# C-06_BOOT_CFG.net
KiCad netlist of a schematic drawn in Altium Designer
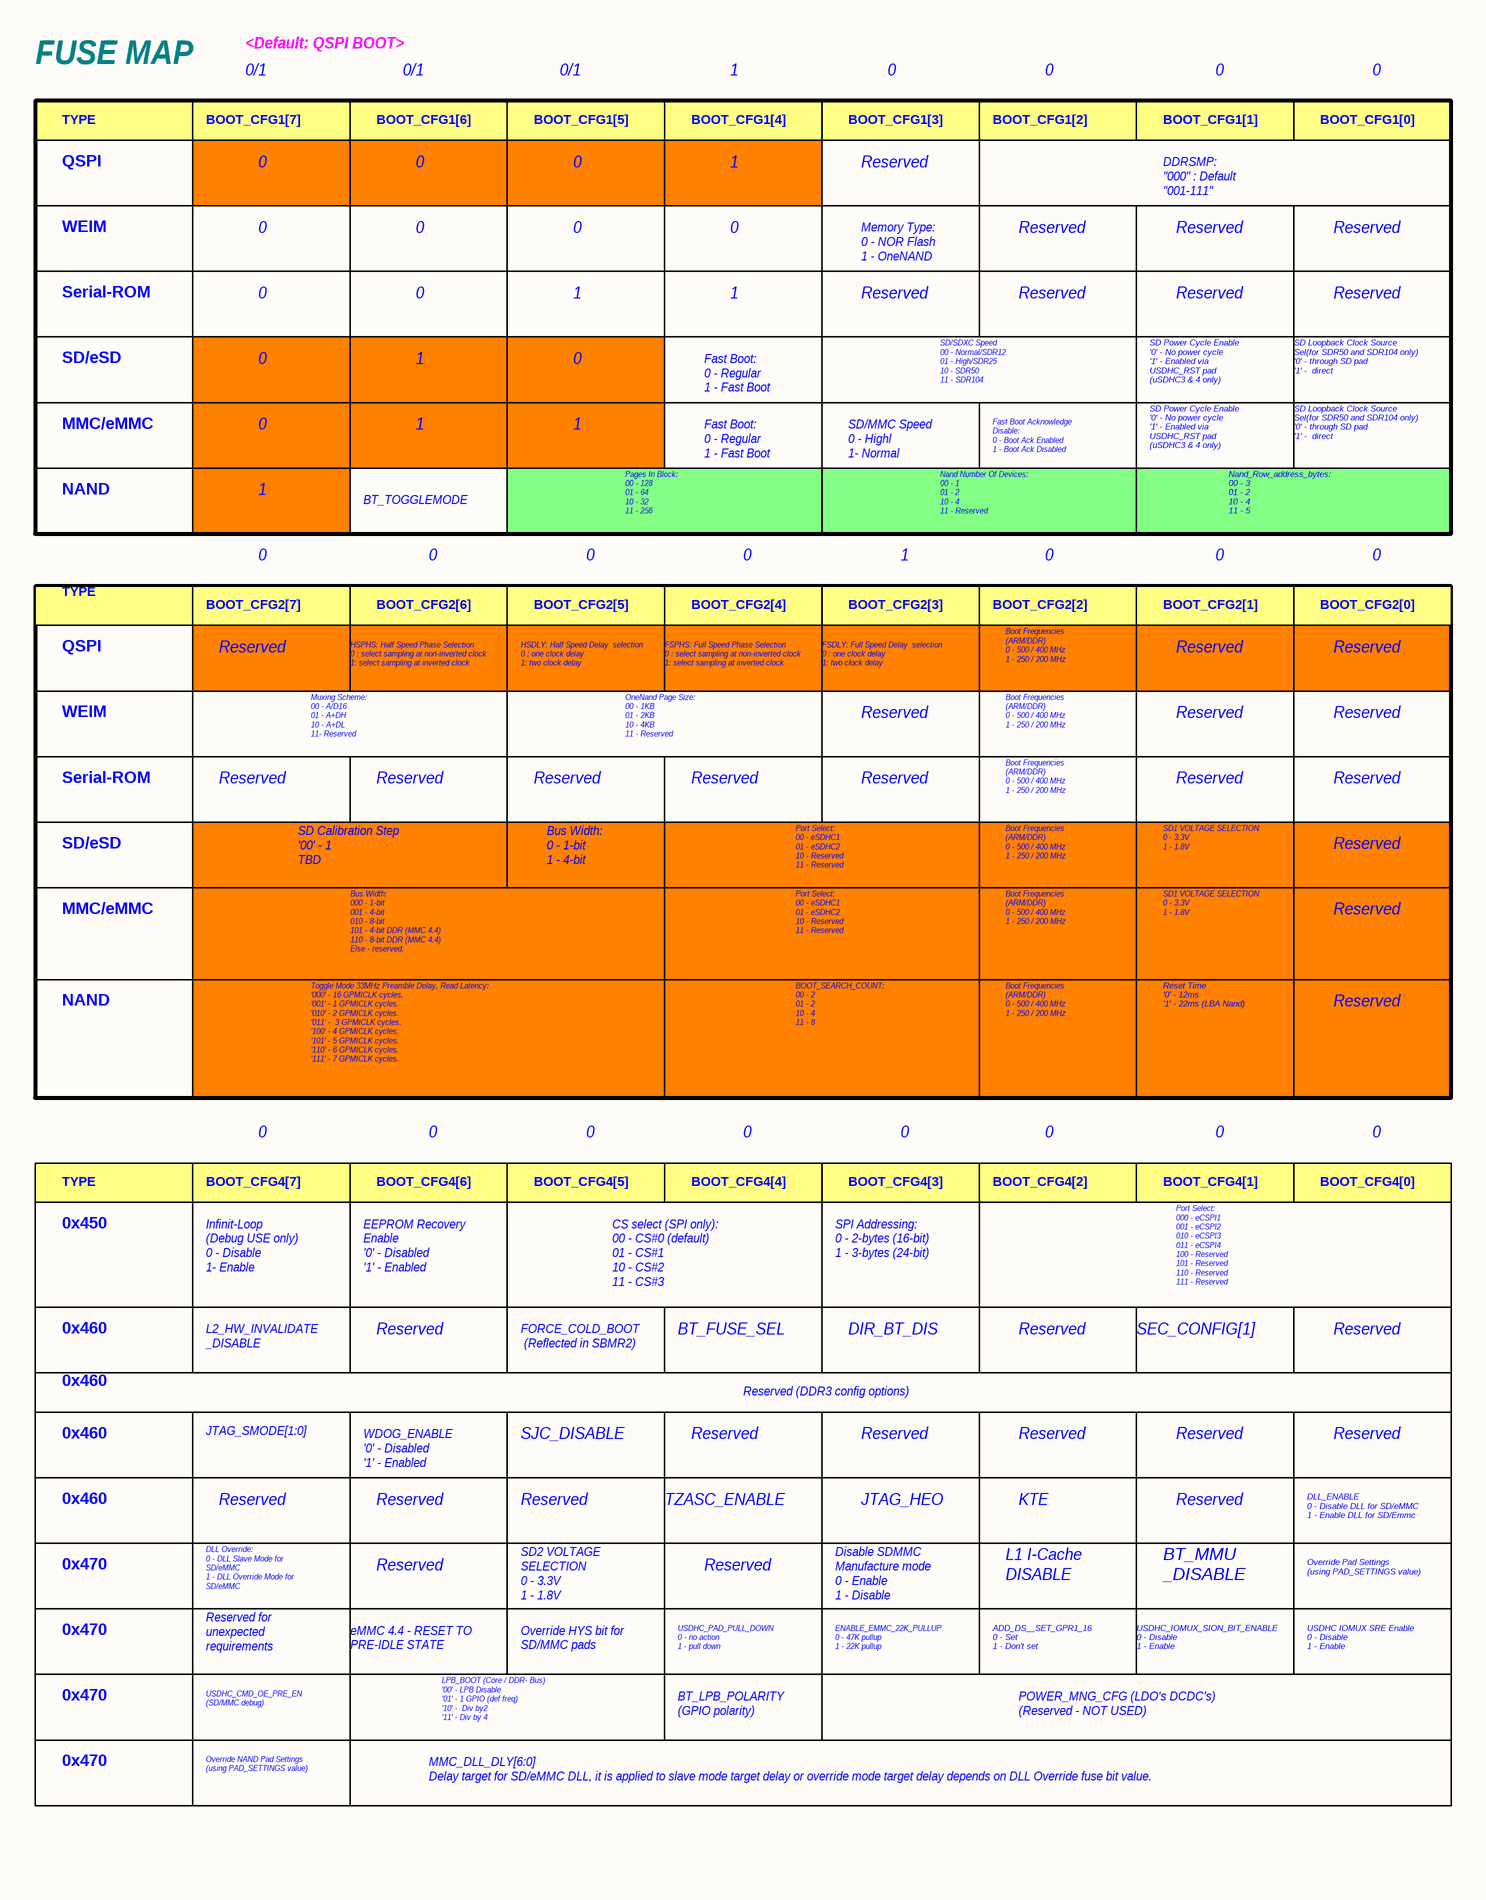
[diagram p0: C-06 BOOT CFG.SchDoc, left]
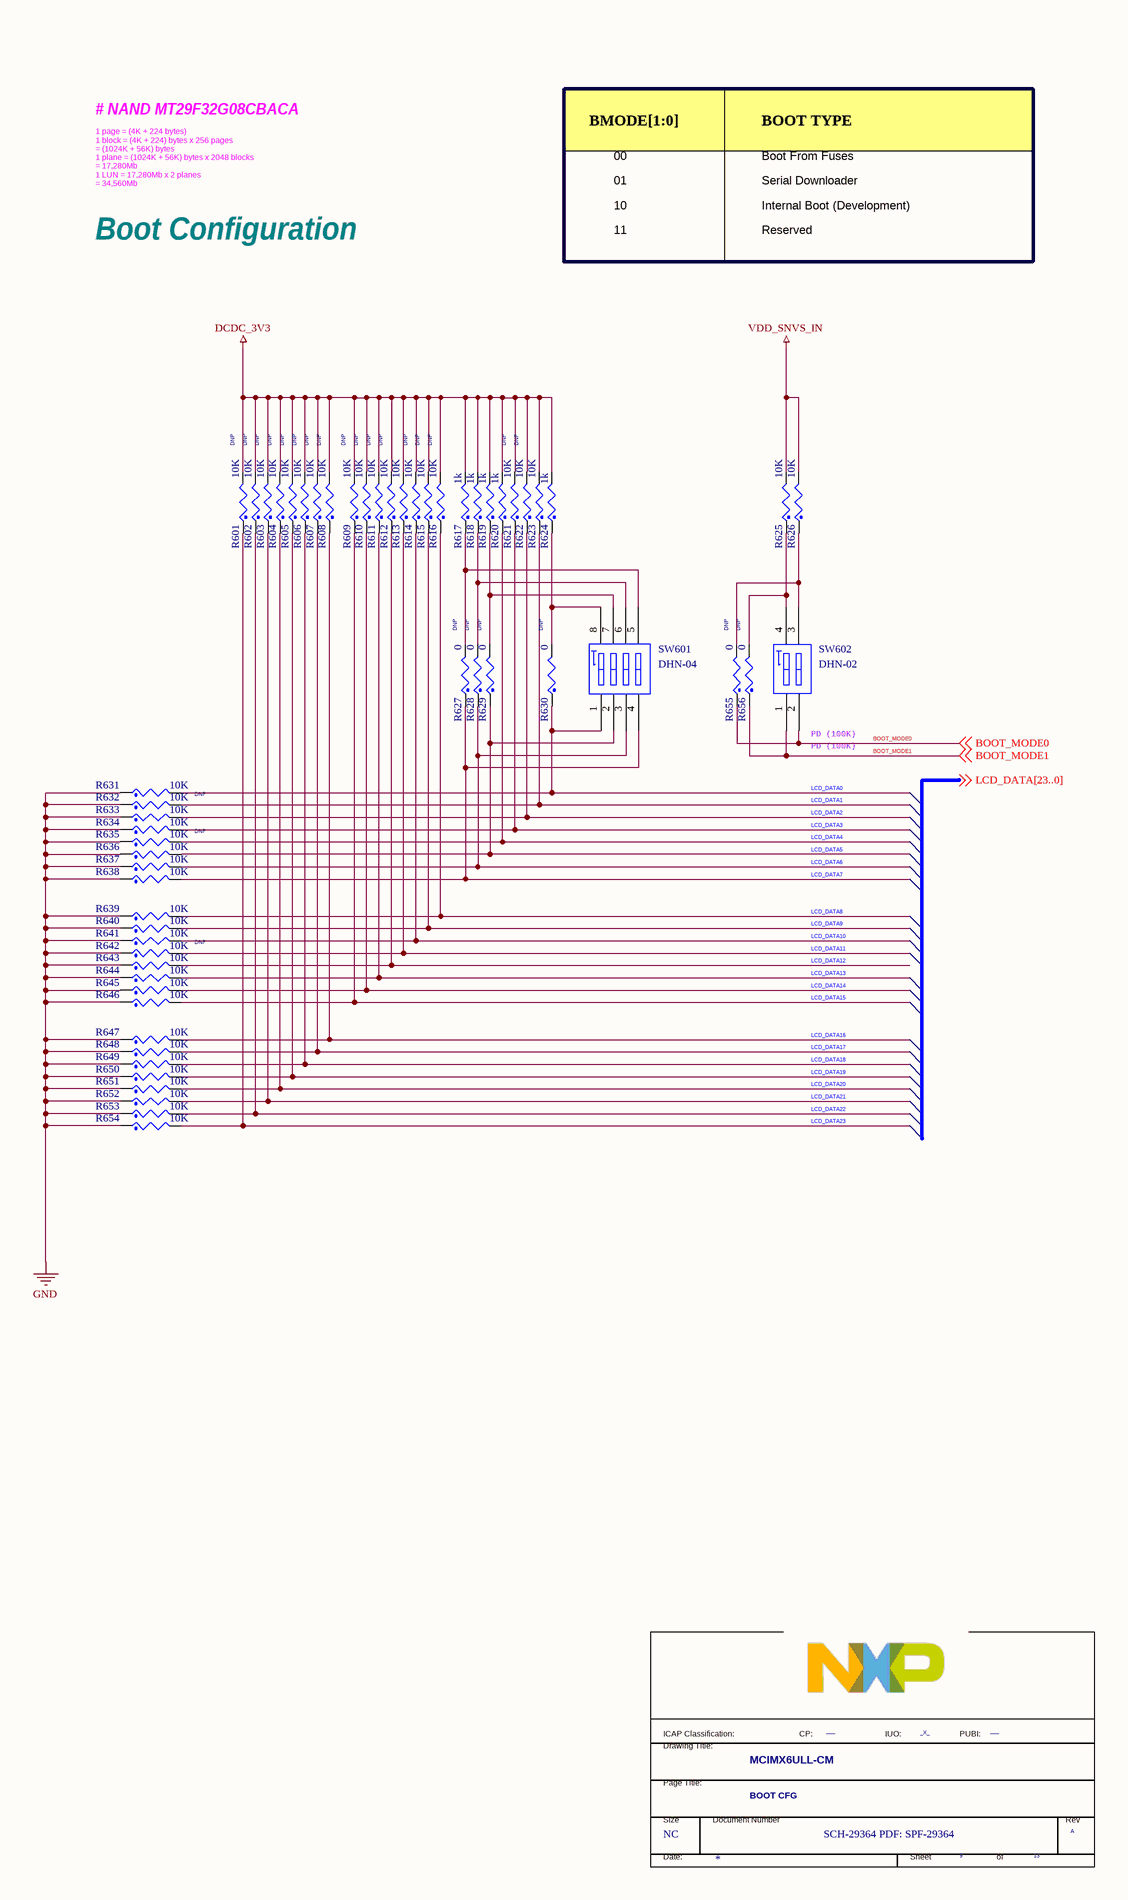
[diagram p1: C-06 BOOT CFG.SchDoc, right]

(export (version "E")
  (design (tool "Eeschema 10.0.6"))
  (components
    (comp (ref "R601")
      (value "10K")
      (footprint "R0402_H0.35mm")
      (description "RES MF 10K 1/16W 5% 0402")
      (fields (field (name "TOLERANCE") "5%") (field (name "ASSY_OPT") "DNP"))
      (libsource (lib "*") (part "RES"))
    )
    (comp (ref "R602")
      (value "10K")
      (footprint "R0402_H0.35mm")
      (description "RES MF 10K 1/16W 5% 0402")
      (fields (field (name "ASSY_OPT") "DNP") (field (name "TOLERANCE") "5%"))
      (libsource (lib "*") (part "RES"))
    )
    (comp (ref "R603")
      (value "10K")
      (footprint "R0402_H0.35mm")
      (description "RES MF 10K 1/16W 5% 0402")
      (fields (field (name "ASSY_OPT") "DNP") (field (name "TOLERANCE") "5%"))
      (libsource (lib "*") (part "RES"))
    )
    (comp (ref "R604")
      (value "10K")
      (footprint "R0402_H0.35mm")
      (description "RES MF 10K 1/16W 5% 0402")
      (fields (field (name "ASSY_OPT") "DNP") (field (name "TOLERANCE") "5%"))
      (libsource (lib "*") (part "RES"))
    )
    (comp (ref "R605")
      (value "10K")
      (footprint "R0402_H0.35mm")
      (description "RES MF 10K 1/16W 5% 0402")
      (fields (field (name "ASSY_OPT") "DNP") (field (name "TOLERANCE") "5%"))
      (libsource (lib "*") (part "RES"))
    )
    (comp (ref "R606")
      (value "10K")
      (footprint "R0402_H0.35mm")
      (description "RES MF 10K 1/16W 5% 0402")
      (fields (field (name "ASSY_OPT") "DNP") (field (name "TOLERANCE") "5%"))
      (libsource (lib "*") (part "RES"))
    )
    (comp (ref "R607")
      (value "10K")
      (footprint "R0402_H0.35mm")
      (description "RES MF 10K 1/16W 5% 0402")
      (fields (field (name "ASSY_OPT") "DNP") (field (name "TOLERANCE") "5%"))
      (libsource (lib "*") (part "RES"))
    )
    (comp (ref "R608")
      (value "10K")
      (footprint "R0402_H0.35mm")
      (description "RES MF 10K 1/16W 5% 0402")
      (fields (field (name "ASSY_OPT") "DNP") (field (name "TOLERANCE") "5%"))
      (libsource (lib "*") (part "RES"))
    )
    (comp (ref "R609")
      (value "10K")
      (footprint "R0402_H0.35mm")
      (description "RES MF 10K 1/16W 5% 0402")
      (fields (field (name "ASSY_OPT") "DNP") (field (name "TOLERANCE") "5%"))
      (libsource (lib "*") (part "RES"))
    )
    (comp (ref "R610")
      (value "10K")
      (footprint "R0402_H0.35mm")
      (description "RES MF 10K 1/16W 5% 0402")
      (fields (field (name "ASSY_OPT") "DNP") (field (name "TOLERANCE") "5%"))
      (libsource (lib "*") (part "RES"))
    )
    (comp (ref "R611")
      (value "10K")
      (footprint "R0402_H0.35mm")
      (description "RES MF 10K 1/16W 5% 0402")
      (fields (field (name "ASSY_OPT") "DNP") (field (name "TOLERANCE") "5%"))
      (libsource (lib "*") (part "RES"))
    )
    (comp (ref "R612")
      (value "10K")
      (footprint "R0402_H0.35mm")
      (description "RES MF 10K 1/16W 5% 0402")
      (fields (field (name "ASSY_OPT") "DNP") (field (name "TOLERANCE") "5%"))
      (libsource (lib "*") (part "RES"))
    )
    (comp (ref "R613")
      (value "10K")
      (footprint "R0402_H0.35mm")
      (description "RES MF 10K 1/16W 5% 0402")
      (fields (field (name "TOLERANCE") "5%"))
      (libsource (lib "*") (part "RES"))
    )
    (comp (ref "R614")
      (value "10K")
      (footprint "R0402_H0.35mm")
      (description "RES MF 10K 1/16W 5% 0402")
      (fields (field (name "ASSY_OPT") "DNP") (field (name "TOLERANCE") "5%"))
      (libsource (lib "*") (part "RES"))
    )
    (comp (ref "R615")
      (value "10K")
      (footprint "R0402_H0.35mm")
      (description "RES MF 10K 1/16W 5% 0402")
      (fields (field (name "ASSY_OPT") "DNP") (field (name "TOLERANCE") "5%"))
      (libsource (lib "*") (part "RES"))
    )
    (comp (ref "R616")
      (value "10K")
      (footprint "R0402_H0.35mm")
      (description "RES MF 10K 1/16W 5% 0402")
      (fields (field (name "ASSY_OPT") "DNP") (field (name "TOLERANCE") "5%"))
      (libsource (lib "*") (part "RES"))
    )
    (comp (ref "R617")
      (value "1k")
      (footprint "R0402_H0.35mm")
      (description "RES MF 1.0K 1/16W 5% 0402")
      (fields (field (name "TOLERANCE") "5%"))
      (libsource (lib "*") (part "RES"))
    )
    (comp (ref "R618")
      (value "1k")
      (footprint "R0402_H0.35mm")
      (description "RES MF 1.0K 1/16W 5% 0402")
      (fields (field (name "TOLERANCE") "5%"))
      (libsource (lib "*") (part "RES"))
    )
    (comp (ref "R619")
      (value "1k")
      (footprint "R0402_H0.35mm")
      (description "RES MF 1.0K 1/16W 5% 0402")
      (fields (field (name "TOLERANCE") "5%"))
      (libsource (lib "*") (part "RES"))
    )
    (comp (ref "R620")
      (value "1k")
      (footprint "R0402_H0.35mm")
      (description "RES MF 1.0K 1/16W 5% 0402")
      (fields (field (name "TOLERANCE") "5%"))
      (libsource (lib "*") (part "RES"))
    )
    (comp (ref "R621")
      (value "10K")
      (footprint "R0402_H0.35mm")
      (description "RES MF 10K 1/16W 5% 0402")
      (fields (field (name "ASSY_OPT") "DNP") (field (name "TOLERANCE") "5%"))
      (libsource (lib "*") (part "RES"))
    )
    (comp (ref "R622")
      (value "10K")
      (footprint "R0402_H0.35mm")
      (description "RES MF 10K 1/16W 5% 0402")
      (fields (field (name "ASSY_OPT") "DNP") (field (name "TOLERANCE") "5%"))
      (libsource (lib "*") (part "RES"))
    )
    (comp (ref "R623")
      (value "10K")
      (footprint "R0402_H0.35mm")
      (description "RES MF 10K 1/16W 5% 0402")
      (fields (field (name "TOLERANCE") "5%"))
      (libsource (lib "*") (part "RES"))
    )
    (comp (ref "R624")
      (value "1k")
      (footprint "R0402_H0.35mm")
      (description "RES MF 1.0K 1/16W 5% 0402")
      (fields (field (name "TOLERANCE") "5%"))
      (libsource (lib "*") (part "RES"))
    )
    (comp (ref "R625")
      (value "10K")
      (footprint "R0402_H0.35mm")
      (description "RES MF 10K 1/16W 5% 0402")
      (fields (field (name "TOLERANCE") "5%"))
      (libsource (lib "*") (part "RES"))
    )
    (comp (ref "R626")
      (value "10K")
      (footprint "R0402_H0.35mm")
      (description "RES MF 10K 1/16W 5% 0402")
      (fields (field (name "TOLERANCE") "5%"))
      (libsource (lib "*") (part "RES"))
    )
    (comp (ref "R627")
      (value "0")
      (footprint "R0402_H0.35mm")
      (description "RES MF ZERO OHM 1/16W 5% 0402")
      (fields (field (name "ASSY_OPT") "DNP") (field (name "TOLERANCE") "5%"))
      (libsource (lib "*") (part "RES"))
    )
    (comp (ref "R628")
      (value "0")
      (footprint "R0402_H0.35mm")
      (description "RES MF ZERO OHM 1/16W 5% 0402")
      (fields (field (name "ASSY_OPT") "DNP") (field (name "TOLERANCE") "5%"))
      (libsource (lib "*") (part "RES"))
    )
    (comp (ref "R629")
      (value "0")
      (footprint "R0402_H0.35mm")
      (description "RES MF ZERO OHM 1/16W 5% 0402")
      (fields (field (name "ASSY_OPT") "DNP") (field (name "TOLERANCE") "5%"))
      (libsource (lib "*") (part "RES"))
    )
    (comp (ref "R630")
      (value "0")
      (footprint "R0402_H0.35mm")
      (description "RES MF ZERO OHM 1/16W 5% 0402")
      (fields (field (name "ASSY_OPT") "DNP") (field (name "TOLERANCE") "5%"))
      (libsource (lib "*") (part "RES"))
    )
    (comp (ref "R631")
      (value "10K")
      (footprint "R0402_H0.35mm")
      (description "RES MF 10K 1/16W 5% 0402")
      (fields (field (name "TOLERANCE") "5%"))
      (libsource (lib "*") (part "RES"))
    )
    (comp (ref "R632")
      (value "10K")
      (footprint "R0402_H0.35mm")
      (description "RES MF 10K 1/16W 5% 0402")
      (fields (field (name "TOLERANCE") "5%") (field (name "ASSY_OPT") "DNP"))
      (libsource (lib "*") (part "RES"))
    )
    (comp (ref "R633")
      (value "10K")
      (footprint "R0402_H0.35mm")
      (description "RES MF 10K 1/16W 5% 0402")
      (fields (field (name "TOLERANCE") "5%"))
      (libsource (lib "*") (part "RES"))
    )
    (comp (ref "R634")
      (value "10K")
      (footprint "R0402_H0.35mm")
      (description "RES MF 10K 1/16W 5% 0402")
      (fields (field (name "TOLERANCE") "5%"))
      (libsource (lib "*") (part "RES"))
    )
    (comp (ref "R635")
      (value "10K")
      (footprint "R0402_H0.35mm")
      (description "RES MF 10K 1/16W 5% 0402")
      (fields (field (name "ASSY_OPT") "DNP") (field (name "TOLERANCE") "5%"))
      (libsource (lib "*") (part "RES"))
    )
    (comp (ref "R636")
      (value "10K")
      (footprint "R0402_H0.35mm")
      (description "RES MF 10K 1/16W 5% 0402")
      (fields (field (name "TOLERANCE") "5%"))
      (libsource (lib "*") (part "RES"))
    )
    (comp (ref "R637")
      (value "10K")
      (footprint "R0402_H0.35mm")
      (description "RES MF 10K 1/16W 5% 0402")
      (fields (field (name "TOLERANCE") "5%"))
      (libsource (lib "*") (part "RES"))
    )
    (comp (ref "R638")
      (value "10K")
      (footprint "R0402_H0.35mm")
      (description "RES MF 10K 1/16W 5% 0402")
      (fields (field (name "TOLERANCE") "5%"))
      (libsource (lib "*") (part "RES"))
    )
    (comp (ref "R639")
      (value "10K")
      (footprint "R0402_H0.35mm")
      (description "RES MF 10K 1/16W 5% 0402")
      (fields (field (name "TOLERANCE") "5%"))
      (libsource (lib "*") (part "RES"))
    )
    (comp (ref "R640")
      (value "10K")
      (footprint "R0402_H0.35mm")
      (description "RES MF 10K 1/16W 5% 0402")
      (fields (field (name "TOLERANCE") "5%"))
      (libsource (lib "*") (part "RES"))
    )
    (comp (ref "R641")
      (value "10K")
      (footprint "R0402_H0.35mm")
      (description "RES MF 10K 1/16W 5% 0402")
      (fields (field (name "TOLERANCE") "5%"))
      (libsource (lib "*") (part "RES"))
    )
    (comp (ref "R642")
      (value "10K")
      (footprint "R0402_H0.35mm")
      (description "RES MF 10K 1/16W 5% 0402")
      (fields (field (name "ASSY_OPT") "DNP") (field (name "TOLERANCE") "5%"))
      (libsource (lib "*") (part "RES"))
    )
    (comp (ref "R643")
      (value "10K")
      (footprint "R0402_H0.35mm")
      (description "RES MF 10K 1/16W 5% 0402")
      (fields (field (name "TOLERANCE") "5%"))
      (libsource (lib "*") (part "RES"))
    )
    (comp (ref "R644")
      (value "10K")
      (footprint "R0402_H0.35mm")
      (description "RES MF 10K 1/16W 5% 0402")
      (fields (field (name "TOLERANCE") "5%"))
      (libsource (lib "*") (part "RES"))
    )
    (comp (ref "R645")
      (value "10K")
      (footprint "R0402_H0.35mm")
      (description "RES MF 10K 1/16W 5% 0402")
      (fields (field (name "TOLERANCE") "5%"))
      (libsource (lib "*") (part "RES"))
    )
    (comp (ref "R646")
      (value "10K")
      (footprint "R0402_H0.35mm")
      (description "RES MF 10K 1/16W 5% 0402")
      (fields (field (name "TOLERANCE") "5%"))
      (libsource (lib "*") (part "RES"))
    )
    (comp (ref "R647")
      (value "10K")
      (footprint "R0402_H0.35mm")
      (description "RES MF 10K 1/16W 5% 0402")
      (fields (field (name "TOLERANCE") "5%"))
      (libsource (lib "*") (part "RES"))
    )
    (comp (ref "R648")
      (value "10K")
      (footprint "R0402_H0.35mm")
      (description "RES MF 10K 1/16W 5% 0402")
      (fields (field (name "TOLERANCE") "5%"))
      (libsource (lib "*") (part "RES"))
    )
    (comp (ref "R649")
      (value "10K")
      (footprint "R0402_H0.35mm")
      (description "RES MF 10K 1/16W 5% 0402")
      (fields (field (name "TOLERANCE") "5%"))
      (libsource (lib "*") (part "RES"))
    )
    (comp (ref "R650")
      (value "10K")
      (footprint "R0402_H0.35mm")
      (description "RES MF 10K 1/16W 5% 0402")
      (fields (field (name "TOLERANCE") "5%"))
      (libsource (lib "*") (part "RES"))
    )
    (comp (ref "R651")
      (value "10K")
      (footprint "R0402_H0.35mm")
      (description "RES MF 10K 1/16W 5% 0402")
      (fields (field (name "TOLERANCE") "5%"))
      (libsource (lib "*") (part "RES"))
    )
    (comp (ref "R652")
      (value "10K")
      (footprint "R0402_H0.35mm")
      (description "RES MF 10K 1/16W 5% 0402")
      (fields (field (name "TOLERANCE") "5%"))
      (libsource (lib "*") (part "RES"))
    )
    (comp (ref "R653")
      (value "10K")
      (footprint "R0402_H0.35mm")
      (description "RES MF 10K 1/16W 5% 0402")
      (fields (field (name "TOLERANCE") "5%"))
      (libsource (lib "*") (part "RES"))
    )
    (comp (ref "R654")
      (value "10K")
      (footprint "R0402_H0.35mm")
      (description "RES MF 10K 1/16W 5% 0402")
      (fields (field (name "TOLERANCE") "5%"))
      (libsource (lib "*") (part "RES"))
    )
    (comp (ref "R655")
      (value "0")
      (footprint "R0402_H0.35mm")
      (description "RES MF ZERO OHM 1/16W 5% 0402")
      (fields (field (name "TOLERANCE") "5%") (field (name "ASSY_OPT") "DNP"))
      (libsource (lib "*") (part "RES"))
    )
    (comp (ref "R656")
      (value "0")
      (footprint "R0402_H0.35mm")
      (description "RES MF ZERO OHM 1/16W 5% 0402")
      (fields (field (name "ASSY_OPT") "DNP") (field (name "TOLERANCE") "5%"))
      (libsource (lib "*") (part "RES"))
    )
    (comp (ref "SW601")
      (value "DHN-04")
      (footprint "DHN-04-V")
      (description "SW 4P SPST DIP 25MA 24V SMT")
      (libsource (lib "*") (part "SW_DIP-4_SM"))
    )
    (comp (ref "SW602")
      (value "DHN-02")
      (footprint "DHN-02-V")
      (description "SW 2P SPST DIP 25MA 24V SMT")
      (libsource (lib "*") (part "SW_DIP-2"))
    )
  )
  (nets
    (net (code "1") (name "BOOT_MODE0") (class "Default")
      (node (ref "R655") (pin "1") (pinfunction "1_1") (pintype "passive"))
      (node (ref "SW602") (pin "2") (pinfunction "A2_2") (pintype "passive"))
    )
    (net (code "2") (name "BOOT_MODE1") (class "Default")
      (node (ref "R656") (pin "1") (pinfunction "1_1") (pintype "passive"))
      (node (ref "SW602") (pin "1") (pinfunction "A1_1") (pintype "passive"))
    )
    (net (code "3") (name "DCDC_3V3") (class "Default")
      (node (ref "R601") (pin "2") (pinfunction "2_2") (pintype "passive"))
      (node (ref "R602") (pin "2") (pinfunction "2_2") (pintype "passive"))
      (node (ref "R603") (pin "2") (pinfunction "2_2") (pintype "passive"))
      (node (ref "R604") (pin "2") (pinfunction "2_2") (pintype "passive"))
      (node (ref "R605") (pin "2") (pinfunction "2_2") (pintype "passive"))
      (node (ref "R606") (pin "2") (pinfunction "2_2") (pintype "passive"))
      (node (ref "R607") (pin "2") (pinfunction "2_2") (pintype "passive"))
      (node (ref "R608") (pin "2") (pinfunction "2_2") (pintype "passive"))
      (node (ref "R609") (pin "2") (pinfunction "2_2") (pintype "passive"))
      (node (ref "R610") (pin "2") (pinfunction "2_2") (pintype "passive"))
      (node (ref "R611") (pin "2") (pinfunction "2_2") (pintype "passive"))
      (node (ref "R612") (pin "2") (pinfunction "2_2") (pintype "passive"))
      (node (ref "R613") (pin "2") (pinfunction "2_2") (pintype "passive"))
      (node (ref "R614") (pin "2") (pinfunction "2_2") (pintype "passive"))
      (node (ref "R615") (pin "2") (pinfunction "2_2") (pintype "passive"))
      (node (ref "R616") (pin "2") (pinfunction "2_2") (pintype "passive"))
      (node (ref "R617") (pin "2") (pinfunction "2_2") (pintype "passive"))
      (node (ref "R618") (pin "2") (pinfunction "2_2") (pintype "passive"))
      (node (ref "R619") (pin "2") (pinfunction "2_2") (pintype "passive"))
      (node (ref "R620") (pin "2") (pinfunction "2_2") (pintype "passive"))
      (node (ref "R621") (pin "2") (pinfunction "2_2") (pintype "passive"))
      (node (ref "R622") (pin "2") (pinfunction "2_2") (pintype "passive"))
      (node (ref "R623") (pin "2") (pinfunction "2_2") (pintype "passive"))
      (node (ref "R624") (pin "2") (pinfunction "2_2") (pintype "passive"))
    )
    (net (code "4") (name "GND") (class "Default")
      (node (ref "R631") (pin "1") (pinfunction "1_1") (pintype "passive"))
      (node (ref "R632") (pin "1") (pinfunction "1_1") (pintype "passive"))
      (node (ref "R633") (pin "1") (pinfunction "1_1") (pintype "passive"))
      (node (ref "R634") (pin "1") (pinfunction "1_1") (pintype "passive"))
      (node (ref "R635") (pin "1") (pinfunction "1_1") (pintype "passive"))
      (node (ref "R636") (pin "1") (pinfunction "1_1") (pintype "passive"))
      (node (ref "R637") (pin "1") (pinfunction "1_1") (pintype "passive"))
      (node (ref "R638") (pin "1") (pinfunction "1_1") (pintype "passive"))
      (node (ref "R639") (pin "1") (pinfunction "1_1") (pintype "passive"))
      (node (ref "R640") (pin "1") (pinfunction "1_1") (pintype "passive"))
      (node (ref "R641") (pin "1") (pinfunction "1_1") (pintype "passive"))
      (node (ref "R642") (pin "1") (pinfunction "1_1") (pintype "passive"))
      (node (ref "R643") (pin "1") (pinfunction "1_1") (pintype "passive"))
      (node (ref "R644") (pin "1") (pinfunction "1_1") (pintype "passive"))
      (node (ref "R645") (pin "1") (pinfunction "1_1") (pintype "passive"))
      (node (ref "R646") (pin "1") (pinfunction "1_1") (pintype "passive"))
      (node (ref "R647") (pin "1") (pinfunction "1_1") (pintype "passive"))
      (node (ref "R648") (pin "1") (pinfunction "1_1") (pintype "passive"))
      (node (ref "R649") (pin "1") (pinfunction "1_1") (pintype "passive"))
      (node (ref "R650") (pin "1") (pinfunction "1_1") (pintype "passive"))
      (node (ref "R651") (pin "1") (pinfunction "1_1") (pintype "passive"))
      (node (ref "R652") (pin "1") (pinfunction "1_1") (pintype "passive"))
      (node (ref "R653") (pin "1") (pinfunction "1_1") (pintype "passive"))
      (node (ref "R654") (pin "1") (pinfunction "1_1") (pintype "passive"))
    )
    (net (code "5") (name "LCD_DATA0") (class "Default")
      (node (ref "R630") (pin "1") (pinfunction "1_1") (pintype "passive"))
      (node (ref "R631") (pin "2") (pinfunction "2_2") (pintype "passive"))
      (node (ref "SW601") (pin "1") (pinfunction "A1_1") (pintype "passive"))
    )
    (net (code "6") (name "LCD_DATA1") (class "Default")
      (node (ref "R623") (pin "1") (pinfunction "1_1") (pintype "passive"))
      (node (ref "R632") (pin "2") (pinfunction "2_2") (pintype "passive"))
    )
    (net (code "7") (name "LCD_DATA2") (class "Default")
      (node (ref "R622") (pin "1") (pinfunction "1_1") (pintype "passive"))
      (node (ref "R633") (pin "2") (pinfunction "2_2") (pintype "passive"))
    )
    (net (code "8") (name "LCD_DATA3") (class "Default")
      (node (ref "R621") (pin "1") (pinfunction "1_1") (pintype "passive"))
      (node (ref "R634") (pin "2") (pinfunction "2_2") (pintype "passive"))
    )
    (net (code "9") (name "LCD_DATA4") (class "Default")
      (node (ref "R620") (pin "1") (pinfunction "1_1") (pintype "passive"))
      (node (ref "R635") (pin "2") (pinfunction "2_2") (pintype "passive"))
    )
    (net (code "10") (name "LCD_DATA5") (class "Default")
      (node (ref "R629") (pin "1") (pinfunction "1_1") (pintype "passive"))
      (node (ref "R636") (pin "2") (pinfunction "2_2") (pintype "passive"))
      (node (ref "SW601") (pin "2") (pinfunction "A2_2") (pintype "passive"))
    )
    (net (code "11") (name "LCD_DATA6") (class "Default")
      (node (ref "R628") (pin "1") (pinfunction "1_1") (pintype "passive"))
      (node (ref "R637") (pin "2") (pinfunction "2_2") (pintype "passive"))
      (node (ref "SW601") (pin "3") (pinfunction "A3_3") (pintype "passive"))
    )
    (net (code "12") (name "LCD_DATA7") (class "Default")
      (node (ref "R627") (pin "1") (pinfunction "1_1") (pintype "passive"))
      (node (ref "R638") (pin "2") (pinfunction "2_2") (pintype "passive"))
      (node (ref "SW601") (pin "4") (pinfunction "A4_4") (pintype "passive"))
    )
    (net (code "13") (name "LCD_DATA8") (class "Default")
      (node (ref "R616") (pin "1") (pinfunction "1_1") (pintype "passive"))
      (node (ref "R639") (pin "2") (pinfunction "2_2") (pintype "passive"))
    )
    (net (code "14") (name "LCD_DATA9") (class "Default")
      (node (ref "R615") (pin "1") (pinfunction "1_1") (pintype "passive"))
      (node (ref "R640") (pin "2") (pinfunction "2_2") (pintype "passive"))
    )
    (net (code "15") (name "LCD_DATA10") (class "Default")
      (node (ref "R614") (pin "1") (pinfunction "1_1") (pintype "passive"))
      (node (ref "R641") (pin "2") (pinfunction "2_2") (pintype "passive"))
    )
    (net (code "16") (name "LCD_DATA11") (class "Default")
      (node (ref "R613") (pin "1") (pinfunction "1_1") (pintype "passive"))
      (node (ref "R642") (pin "2") (pinfunction "2_2") (pintype "passive"))
    )
    (net (code "17") (name "LCD_DATA12") (class "Default")
      (node (ref "R612") (pin "1") (pinfunction "1_1") (pintype "passive"))
      (node (ref "R643") (pin "2") (pinfunction "2_2") (pintype "passive"))
    )
    (net (code "18") (name "LCD_DATA13") (class "Default")
      (node (ref "R611") (pin "1") (pinfunction "1_1") (pintype "passive"))
      (node (ref "R644") (pin "2") (pinfunction "2_2") (pintype "passive"))
    )
    (net (code "19") (name "LCD_DATA14") (class "Default")
      (node (ref "R610") (pin "1") (pinfunction "1_1") (pintype "passive"))
      (node (ref "R645") (pin "2") (pinfunction "2_2") (pintype "passive"))
    )
    (net (code "20") (name "LCD_DATA15") (class "Default")
      (node (ref "R609") (pin "1") (pinfunction "1_1") (pintype "passive"))
      (node (ref "R646") (pin "2") (pinfunction "2_2") (pintype "passive"))
    )
    (net (code "21") (name "LCD_DATA16") (class "Default")
      (node (ref "R608") (pin "1") (pinfunction "1_1") (pintype "passive"))
      (node (ref "R647") (pin "2") (pinfunction "2_2") (pintype "passive"))
    )
    (net (code "22") (name "LCD_DATA17") (class "Default")
      (node (ref "R607") (pin "1") (pinfunction "1_1") (pintype "passive"))
      (node (ref "R648") (pin "2") (pinfunction "2_2") (pintype "passive"))
    )
    (net (code "23") (name "LCD_DATA18") (class "Default")
      (node (ref "R606") (pin "1") (pinfunction "1_1") (pintype "passive"))
      (node (ref "R649") (pin "2") (pinfunction "2_2") (pintype "passive"))
    )
    (net (code "24") (name "LCD_DATA19") (class "Default")
      (node (ref "R605") (pin "1") (pinfunction "1_1") (pintype "passive"))
      (node (ref "R650") (pin "2") (pinfunction "2_2") (pintype "passive"))
    )
    (net (code "25") (name "LCD_DATA20") (class "Default")
      (node (ref "R604") (pin "1") (pinfunction "1_1") (pintype "passive"))
      (node (ref "R651") (pin "2") (pinfunction "2_2") (pintype "passive"))
    )
    (net (code "26") (name "LCD_DATA21") (class "Default")
      (node (ref "R603") (pin "1") (pinfunction "1_1") (pintype "passive"))
      (node (ref "R652") (pin "2") (pinfunction "2_2") (pintype "passive"))
    )
    (net (code "27") (name "LCD_DATA22") (class "Default")
      (node (ref "R602") (pin "1") (pinfunction "1_1") (pintype "passive"))
      (node (ref "R653") (pin "2") (pinfunction "2_2") (pintype "passive"))
    )
    (net (code "28") (name "LCD_DATA23") (class "Default")
      (node (ref "R601") (pin "1") (pinfunction "1_1") (pintype "passive"))
      (node (ref "R654") (pin "2") (pinfunction "2_2") (pintype "passive"))
    )
    (net (code "30") (name "Net-(SW601-B1)") (class "Default")
      (node (ref "R624") (pin "1") (pinfunction "1_1") (pintype "passive"))
      (node (ref "R630") (pin "2") (pinfunction "2_2") (pintype "passive"))
      (node (ref "SW601") (pin "8") (pinfunction "B1_8") (pintype "passive"))
    )
    (net (code "31") (name "Net-(SW601-B2)") (class "Default")
      (node (ref "R619") (pin "1") (pinfunction "1_1") (pintype "passive"))
      (node (ref "R629") (pin "2") (pinfunction "2_2") (pintype "passive"))
      (node (ref "SW601") (pin "7") (pinfunction "B2_7") (pintype "passive"))
    )
    (net (code "32") (name "Net-(SW601-B3)") (class "Default")
      (node (ref "R618") (pin "1") (pinfunction "1_1") (pintype "passive"))
      (node (ref "R628") (pin "2") (pinfunction "2_2") (pintype "passive"))
      (node (ref "SW601") (pin "6") (pinfunction "B3_6") (pintype "passive"))
    )
    (net (code "33") (name "Net-(SW601-B4)") (class "Default")
      (node (ref "R617") (pin "1") (pinfunction "1_1") (pintype "passive"))
      (node (ref "R627") (pin "2") (pinfunction "2_2") (pintype "passive"))
      (node (ref "SW601") (pin "5") (pinfunction "B4_5") (pintype "passive"))
    )
    (net (code "34") (name "Net-(SW602-B1)") (class "Default")
      (node (ref "R625") (pin "1") (pinfunction "1_1") (pintype "passive"))
      (node (ref "R656") (pin "2") (pinfunction "2_2") (pintype "passive"))
      (node (ref "SW602") (pin "4") (pinfunction "B1_4") (pintype "passive"))
    )
    (net (code "35") (name "Net-(SW602-B2)") (class "Default")
      (node (ref "R626") (pin "1") (pinfunction "1_1") (pintype "passive"))
      (node (ref "R655") (pin "2") (pinfunction "2_2") (pintype "passive"))
      (node (ref "SW602") (pin "3") (pinfunction "B2_3") (pintype "passive"))
    )
    (net (code "36") (name "VDD_SNVS_IN") (class "Default")
      (node (ref "R625") (pin "2") (pinfunction "2_2") (pintype "passive"))
      (node (ref "R626") (pin "2") (pinfunction "2_2") (pintype "passive"))
    )
  )
)
